# Sensor_Acquisition_Board_Rev4.net
KiCad netlist of a schematic drawn in EAGLE
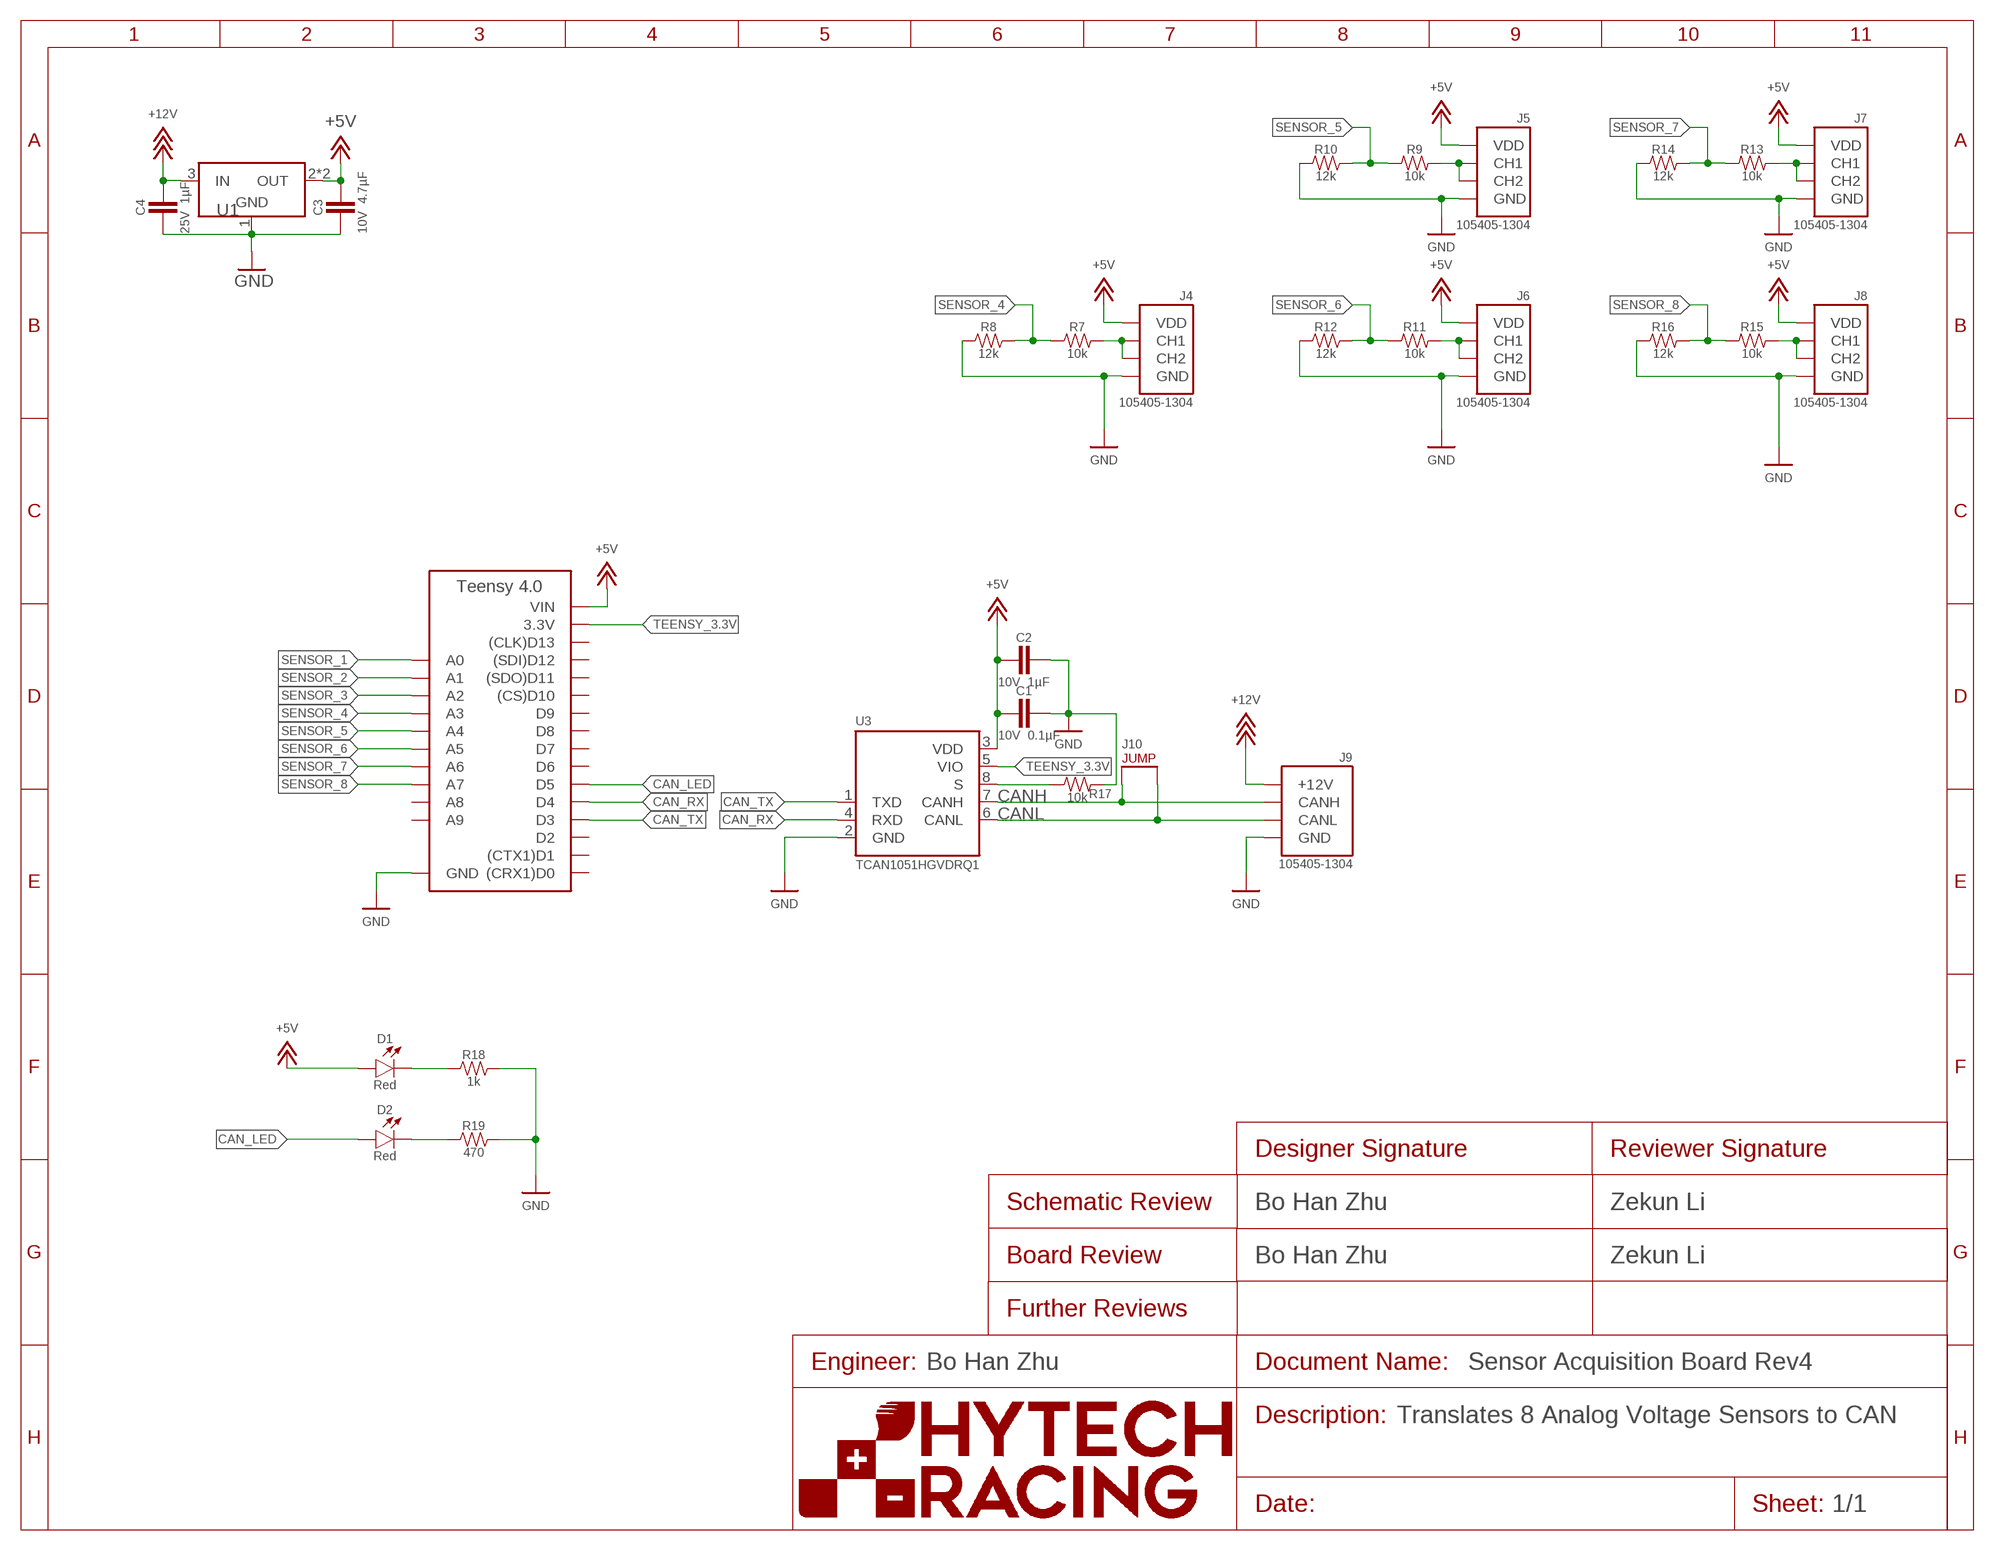
[diagram p0: schematic, sheet 1]

(export (version "E")
  (design (tool "Eeschema 10.0.6"))
  (components
    (comp (ref "A2")
      (value "TEENSY_4.0")
      (footprint "eagle-import:TEENSY_SHORT")
      (libsource (lib "eagle-import") (part "TEENSY_4.0"))
    )
    (comp (ref "C1")
      (value "CAPACITOR_0603_10V_0.1UF")
      (footprint "eagle-import:0603-CAP")
      (fields
        (field (name "CAPACITANCE") "0.1µF")
        (field (name "MANUFACTURER") "Vishay Vitramon")
        (field (name "MPN") "VJ0603Y104JXQPW1BC")
        (field (name "TOLERANCE") "5%")
        (field (name "VOLTAGE") "10V")
      )
      (libsource (lib "eagle-import") (part "CAPACITOR_?_060310V_0.1UF"))
    )
    (comp (ref "C2")
      (value "CAPACITOR_0603_10V_1UF")
      (footprint "eagle-import:0603-CAP")
      (fields
        (field (name "CAPACITANCE") "1µF")
        (field (name "MANUFACTURER") "Yageo")
        (field (name "MPN") "CC0603KRX7R6BB105")
        (field (name "TOLERANCE") "10%")
        (field (name "VOLTAGE") "10V")
      )
      (libsource (lib "eagle-import") (part "CAPACITOR_?_060310V_1UF"))
    )
    (comp (ref "C3")
      (value "CAPACITOR_0603_10V_4.7UF")
      (footprint "eagle-import:0603-CAP")
      (fields
        (field (name "CAPACITANCE") "4.7µF")
        (field (name "MANUFACTURER") "Samsung Electro-Mechanics")
        (field (name "MPN") "CL10A475KP8NNNC")
        (field (name "TOLERANCE") "10%")
        (field (name "VOLTAGE") "10V")
      )
      (libsource (lib "eagle-import") (part "CAPACITOR_?_060310V_4.7UF"))
    )
    (comp (ref "C4")
      (value "CAPACITOR_0603_25V_1UF")
      (footprint "eagle-import:0603-CAP")
      (fields
        (field (name "CAPACITANCE") "1µF")
        (field (name "MANUFACTURER") "Samsung Electro-Mechanics")
        (field (name "MPN") "CL10B105KA8NNNC")
        (field (name "TOLERANCE") "10%")
        (field (name "VOLTAGE") "25V")
      )
      (libsource (lib "eagle-import") (part "CAPACITOR_?_060325V_1UF"))
    )
    (comp (ref "D1")
      (value "LED_0603_RED")
      (footprint "eagle-import:0603-LED")
      (fields
        (field (name "COLOR") "Red")
        (field (name "MANUFACTURER") "Kingbright")
        (field (name "MPN") "APT1608SECK/J3-PRV")
      )
      (libsource (lib "eagle-import") (part "LED_?_0603RED"))
    )
    (comp (ref "D2")
      (value "LED_0603_RED")
      (footprint "eagle-import:0603-LED")
      (fields
        (field (name "COLOR") "Red")
        (field (name "MANUFACTURER") "Kingbright")
        (field (name "MPN") "APT1608SECK/J3-PRV")
      )
      (libsource (lib "eagle-import") (part "LED_?_0603RED"))
    )
    (comp (ref "J4")
      (value "CONNECTOR-SENSOR_NF_S_RA_BLACK")
      (footprint "eagle-import:MOLEX_NANOFIT_SMD_RIGHTANGLE_04")
      (fields (field (name "MANUFACTURER") "Molex") (field (name "MPN") "105405-1304"))
      (libsource (lib "eagle-import") (part "CONNECTOR-SENSOR_?_NF_S_RABLACK"))
    )
    (comp (ref "J5")
      (value "CONNECTOR-SENSOR_NF_S_RA_BLACK")
      (footprint "eagle-import:MOLEX_NANOFIT_SMD_RIGHTANGLE_04")
      (fields (field (name "MANUFACTURER") "Molex") (field (name "MPN") "105405-1304"))
      (libsource (lib "eagle-import") (part "CONNECTOR-SENSOR_?_NF_S_RABLACK"))
    )
    (comp (ref "J6")
      (value "CONNECTOR-SENSOR_NF_S_RA_BLACK")
      (footprint "eagle-import:MOLEX_NANOFIT_SMD_RIGHTANGLE_04")
      (fields (field (name "MANUFACTURER") "Molex") (field (name "MPN") "105405-1304"))
      (libsource (lib "eagle-import") (part "CONNECTOR-SENSOR_?_NF_S_RABLACK"))
    )
    (comp (ref "J7")
      (value "CONNECTOR-SENSOR_NF_S_RA_BLACK")
      (footprint "eagle-import:MOLEX_NANOFIT_SMD_RIGHTANGLE_04")
      (fields (field (name "MANUFACTURER") "Molex") (field (name "MPN") "105405-1304"))
      (libsource (lib "eagle-import") (part "CONNECTOR-SENSOR_?_NF_S_RABLACK"))
    )
    (comp (ref "J8")
      (value "CONNECTOR-SENSOR_NF_S_RA_BLACK")
      (footprint "eagle-import:MOLEX_NANOFIT_SMD_RIGHTANGLE_04")
      (fields (field (name "MANUFACTURER") "Molex") (field (name "MPN") "105405-1304"))
      (libsource (lib "eagle-import") (part "CONNECTOR-SENSOR_?_NF_S_RABLACK"))
    )
    (comp (ref "J9")
      (value "CONNECTOR-CAN_NF_S_RA_BLACK")
      (footprint "eagle-import:MOLEX_NANOFIT_SMD_RIGHTANGLE_04")
      (fields (field (name "MANUFACTURER") "Molex") (field (name "MPN") "105405-1304"))
      (libsource (lib "eagle-import") (part "CONNECTOR-CAN_?_NF_S_RABLACK"))
    )
    (comp (ref "J10")
      (value "JUMPER_0603_")
      (footprint "eagle-import:0603-RES")
      (fields (field (name "MPN") "RC0603FR-130RL") (field (name "MANUFACTURER") "YAGEO"))
      (libsource (lib "eagle-import") (part "JUMPER_?_0603"))
    )
    (comp (ref "R7")
      (value "RESISTOR_0603_10K")
      (footprint "eagle-import:0603-RES")
      (fields
        (field (name "MANUFACTURER") "Yageo")
        (field (name "MPN") "RC0603FR-0710KL")
        (field (name "POWER") "0.1W")
        (field (name "RESISTANCE") "10k")
      )
      (libsource (lib "eagle-import") (part "RESISTOR_?_060310K"))
    )
    (comp (ref "R8")
      (value "RESISTOR_0603_12K")
      (footprint "eagle-import:0603-RES")
      (fields
        (field (name "MANUFACTURER") "Yageo")
        (field (name "MPN") "RC0603FR-0712KL")
        (field (name "POWER") "0.1W")
        (field (name "RESISTANCE") "12k")
      )
      (libsource (lib "eagle-import") (part "RESISTOR_?_060312K"))
    )
    (comp (ref "R9")
      (value "RESISTOR_0603_10K")
      (footprint "eagle-import:0603-RES")
      (fields
        (field (name "MANUFACTURER") "Yageo")
        (field (name "MPN") "RC0603FR-0710KL")
        (field (name "POWER") "0.1W")
        (field (name "RESISTANCE") "10k")
      )
      (libsource (lib "eagle-import") (part "RESISTOR_?_060310K"))
    )
    (comp (ref "R10")
      (value "RESISTOR_0603_12K")
      (footprint "eagle-import:0603-RES")
      (fields
        (field (name "MANUFACTURER") "Yageo")
        (field (name "MPN") "RC0603FR-0712KL")
        (field (name "POWER") "0.1W")
        (field (name "RESISTANCE") "12k")
      )
      (libsource (lib "eagle-import") (part "RESISTOR_?_060312K"))
    )
    (comp (ref "R11")
      (value "RESISTOR_0603_10K")
      (footprint "eagle-import:0603-RES")
      (fields
        (field (name "MANUFACTURER") "Yageo")
        (field (name "MPN") "RC0603FR-0710KL")
        (field (name "POWER") "0.1W")
        (field (name "RESISTANCE") "10k")
      )
      (libsource (lib "eagle-import") (part "RESISTOR_?_060310K"))
    )
    (comp (ref "R12")
      (value "RESISTOR_0603_12K")
      (footprint "eagle-import:0603-RES")
      (fields
        (field (name "MANUFACTURER") "Yageo")
        (field (name "MPN") "RC0603FR-0712KL")
        (field (name "POWER") "0.1W")
        (field (name "RESISTANCE") "12k")
      )
      (libsource (lib "eagle-import") (part "RESISTOR_?_060312K"))
    )
    (comp (ref "R13")
      (value "RESISTOR_0603_10K")
      (footprint "eagle-import:0603-RES")
      (fields
        (field (name "MANUFACTURER") "Yageo")
        (field (name "MPN") "RC0603FR-0710KL")
        (field (name "POWER") "0.1W")
        (field (name "RESISTANCE") "10k")
      )
      (libsource (lib "eagle-import") (part "RESISTOR_?_060310K"))
    )
    (comp (ref "R14")
      (value "RESISTOR_0603_12K")
      (footprint "eagle-import:0603-RES")
      (fields
        (field (name "MANUFACTURER") "Yageo")
        (field (name "MPN") "RC0603FR-0712KL")
        (field (name "POWER") "0.1W")
        (field (name "RESISTANCE") "12k")
      )
      (libsource (lib "eagle-import") (part "RESISTOR_?_060312K"))
    )
    (comp (ref "R15")
      (value "RESISTOR_0603_10K")
      (footprint "eagle-import:0603-RES")
      (fields
        (field (name "MANUFACTURER") "Yageo")
        (field (name "MPN") "RC0603FR-0710KL")
        (field (name "POWER") "0.1W")
        (field (name "RESISTANCE") "10k")
      )
      (libsource (lib "eagle-import") (part "RESISTOR_?_060310K"))
    )
    (comp (ref "R16")
      (value "RESISTOR_0603_12K")
      (footprint "eagle-import:0603-RES")
      (fields
        (field (name "MANUFACTURER") "Yageo")
        (field (name "MPN") "RC0603FR-0712KL")
        (field (name "POWER") "0.1W")
        (field (name "RESISTANCE") "12k")
      )
      (libsource (lib "eagle-import") (part "RESISTOR_?_060312K"))
    )
    (comp (ref "R17")
      (value "RESISTOR_0603_10K")
      (footprint "eagle-import:0603-RES")
      (fields
        (field (name "MANUFACTURER") "Yageo")
        (field (name "MPN") "RC0603FR-0710KL")
        (field (name "POWER") "0.1W")
        (field (name "RESISTANCE") "10k")
      )
      (libsource (lib "eagle-import") (part "RESISTOR_?_060310K"))
    )
    (comp (ref "R18")
      (value "RESISTOR_0603_1K")
      (footprint "eagle-import:0603-RES")
      (fields
        (field (name "MANUFACTURER") "Yageo")
        (field (name "MPN") "RC0603FR-071KL")
        (field (name "POWER") "0.1W")
        (field (name "RESISTANCE") "1k")
      )
      (libsource (lib "eagle-import") (part "RESISTOR_?_06031K"))
    )
    (comp (ref "R19")
      (value "RESISTOR_0603_470")
      (footprint "eagle-import:0603-RES")
      (fields
        (field (name "MANUFACTURER") "Panasonic Electronic Components")
        (field (name "MPN") "ERJ-PA3F4700V")
        (field (name "POWER") "0.25W")
        (field (name "RESISTANCE") "470")
      )
      (libsource (lib "eagle-import") (part "RESISTOR_?_0603470"))
    )
    (comp (ref "U1")
      (value "VOLTAGE_REGULATOR_SOT-223_5V")
      (footprint "eagle-import:SOT-223")
      (fields (field (name "MANUFACTURER") "STMicroelectronics") (field (name "MPN") "LDL1117S50R"))
      (libsource (lib "eagle-import") (part "VOLTAGE_REGULATOR_?_SOT-2235V"))
    )
    (comp (ref "U3")
      (value "TCAN1051HQV-Q1")
      (footprint "eagle-import:SOIC-08(NARROW,0.15_)")
      (fields (field (name "MANUFACTURER") "Texas Instruments") (field (name "MPN") "TCAN1051HGVDRQ1"))
      (libsource (lib "eagle-import") (part "TCAN1051V-Q1HQ"))
    )
  )
  (nets
    (net (code "1") (name "+5V") (class "Default")
      (node (ref "A2") (pin "VIN") (pinfunction "VIN_VIN") (pintype "power_in"))
      (node (ref "C1") (pin "2") (pinfunction "2_2") (pintype "passive"))
      (node (ref "C2") (pin "2") (pinfunction "2_2") (pintype "passive"))
      (node (ref "C3") (pin "1") (pinfunction "1_1") (pintype "passive"))
      (node (ref "D1") (pin "2") (pinfunction "A_2") (pintype "passive"))
      (node (ref "J4") (pin "1") (pinfunction "VDD_1") (pintype "power_in"))
      (node (ref "J5") (pin "1") (pinfunction "VDD_1") (pintype "power_in"))
      (node (ref "J6") (pin "1") (pinfunction "VDD_1") (pintype "power_in"))
      (node (ref "J7") (pin "1") (pinfunction "VDD_1") (pintype "power_in"))
      (node (ref "J8") (pin "1") (pinfunction "VDD_1") (pintype "power_in"))
      (node (ref "U1") (pin "2") (pinfunction "OUT_2") (pintype "power_in"))
      (node (ref "U1") (pin "4") (pinfunction "OUT_4") (pintype "power_in"))
      (node (ref "U3") (pin "3") (pinfunction "VDD_3") (pintype "power_in"))
    )
    (net (code "2") (name "+12V") (class "Default")
      (node (ref "C4") (pin "1") (pinfunction "1_1") (pintype "passive"))
      (node (ref "J9") (pin "1") (pinfunction "+12V_1") (pintype "power_in"))
      (node (ref "U1") (pin "3") (pinfunction "IN_3") (pintype "power_in"))
    )
    (net (code "3") (name "/CANH") (class "Default")
      (node (ref "J10") (pin "1") (pinfunction "1_1") (pintype "passive"))
      (node (ref "J9") (pin "4") (pinfunction "CANH_4") (pintype "bidirectional"))
      (node (ref "U3") (pin "7") (pinfunction "CANH_7") (pintype "output"))
    )
    (net (code "4") (name "/CANL") (class "Default")
      (node (ref "J10") (pin "2") (pinfunction "2_2") (pintype "passive"))
      (node (ref "J9") (pin "3") (pinfunction "CANL_3") (pintype "bidirectional"))
      (node (ref "U3") (pin "6") (pinfunction "CANL_6") (pintype "bidirectional"))
    )
    (net (code "5") (name "CAN_LED") (class "Default")
      (node (ref "A2") (pin "D5") (pinfunction "D5_D5") (pintype "bidirectional"))
      (node (ref "D2") (pin "2") (pinfunction "A_2") (pintype "passive"))
    )
    (net (code "6") (name "CAN_RX") (class "Default")
      (node (ref "A2") (pin "D4") (pinfunction "D4_D4") (pintype "bidirectional"))
      (node (ref "U3") (pin "4") (pinfunction "RXD_4") (pintype "output"))
    )
    (net (code "7") (name "CAN_TX") (class "Default")
      (node (ref "A2") (pin "D3") (pinfunction "D3_D3") (pintype "bidirectional"))
      (node (ref "U3") (pin "1") (pinfunction "TXD_1") (pintype "input"))
    )
    (net (code "8") (name "GND") (class "Default")
      (node (ref "A2") (pin "AGND/GND") (pinfunction "GND_AGND/GND") (pintype "power_in"))
      (node (ref "A2") (pin "GND") (pinfunction "GND_GND") (pintype "power_in"))
      (node (ref "C1") (pin "1") (pinfunction "1_1") (pintype "passive"))
      (node (ref "C2") (pin "1") (pinfunction "1_1") (pintype "passive"))
      (node (ref "C3") (pin "2") (pinfunction "2_2") (pintype "passive"))
      (node (ref "C4") (pin "2") (pinfunction "2_2") (pintype "passive"))
      (node (ref "J4") (pin "2") (pinfunction "GND_2") (pintype "power_in"))
      (node (ref "J5") (pin "2") (pinfunction "GND_2") (pintype "power_in"))
      (node (ref "J6") (pin "2") (pinfunction "GND_2") (pintype "power_in"))
      (node (ref "J7") (pin "2") (pinfunction "GND_2") (pintype "power_in"))
      (node (ref "J8") (pin "2") (pinfunction "GND_2") (pintype "power_in"))
      (node (ref "J9") (pin "2") (pinfunction "GND_2") (pintype "power_in"))
      (node (ref "R10") (pin "1") (pinfunction "1_1") (pintype "passive"))
      (node (ref "R12") (pin "1") (pinfunction "1_1") (pintype "passive"))
      (node (ref "R14") (pin "1") (pinfunction "1_1") (pintype "passive"))
      (node (ref "R16") (pin "1") (pinfunction "1_1") (pintype "passive"))
      (node (ref "R17") (pin "2") (pinfunction "2_2") (pintype "passive"))
      (node (ref "R18") (pin "2") (pinfunction "2_2") (pintype "passive"))
      (node (ref "R19") (pin "2") (pinfunction "2_2") (pintype "passive"))
      (node (ref "R8") (pin "1") (pinfunction "1_1") (pintype "passive"))
      (node (ref "U1") (pin "1") (pinfunction "GND_1") (pintype "power_in"))
      (node (ref "U3") (pin "2") (pinfunction "GND_2") (pintype "power_in"))
    )
    (net (code "9") (name "Net-(D1-C)") (class "Default")
      (node (ref "D1") (pin "1") (pinfunction "C_1") (pintype "passive"))
      (node (ref "R18") (pin "1") (pinfunction "1_1") (pintype "passive"))
    )
    (net (code "10") (name "Net-(D2-C)") (class "Default")
      (node (ref "D2") (pin "1") (pinfunction "C_1") (pintype "passive"))
      (node (ref "R19") (pin "1") (pinfunction "1_1") (pintype "passive"))
    )
    (net (code "11") (name "Net-(J4-CH1)") (class "Default")
      (node (ref "J4") (pin "3") (pinfunction "CH1_3") (pintype "output"))
      (node (ref "J4") (pin "4") (pinfunction "CH2_4") (pintype "output"))
      (node (ref "R7") (pin "2") (pinfunction "2_2") (pintype "passive"))
    )
    (net (code "12") (name "Net-(J5-CH1)") (class "Default")
      (node (ref "J5") (pin "3") (pinfunction "CH1_3") (pintype "output"))
      (node (ref "J5") (pin "4") (pinfunction "CH2_4") (pintype "output"))
      (node (ref "R9") (pin "2") (pinfunction "2_2") (pintype "passive"))
    )
    (net (code "13") (name "Net-(J6-CH1)") (class "Default")
      (node (ref "J6") (pin "3") (pinfunction "CH1_3") (pintype "output"))
      (node (ref "J6") (pin "4") (pinfunction "CH2_4") (pintype "output"))
      (node (ref "R11") (pin "2") (pinfunction "2_2") (pintype "passive"))
    )
    (net (code "14") (name "Net-(J7-CH1)") (class "Default")
      (node (ref "J7") (pin "3") (pinfunction "CH1_3") (pintype "output"))
      (node (ref "J7") (pin "4") (pinfunction "CH2_4") (pintype "output"))
      (node (ref "R13") (pin "2") (pinfunction "2_2") (pintype "passive"))
    )
    (net (code "15") (name "Net-(J8-CH1)") (class "Default")
      (node (ref "J8") (pin "3") (pinfunction "CH1_3") (pintype "output"))
      (node (ref "J8") (pin "4") (pinfunction "CH2_4") (pintype "output"))
      (node (ref "R15") (pin "2") (pinfunction "2_2") (pintype "passive"))
    )
    (net (code "16") (name "Net-(U3-S)") (class "Default")
      (node (ref "R17") (pin "1") (pinfunction "1_1") (pintype "passive"))
      (node (ref "U3") (pin "8") (pinfunction "S_8") (pintype "input"))
    )
    (net (code "17") (name "SENSOR_1") (class "Default")
      (node (ref "A2") (pin "D14") (pinfunction "A0_D14") (pintype "bidirectional"))
    )
    (net (code "18") (name "SENSOR_2") (class "Default")
      (node (ref "A2") (pin "D15") (pinfunction "A1_D15") (pintype "bidirectional"))
    )
    (net (code "19") (name "SENSOR_3") (class "Default")
      (node (ref "A2") (pin "D16") (pinfunction "A2_D16") (pintype "bidirectional"))
    )
    (net (code "20") (name "SENSOR_4") (class "Default")
      (node (ref "A2") (pin "D17") (pinfunction "A3_D17") (pintype "bidirectional"))
      (node (ref "R7") (pin "1") (pinfunction "1_1") (pintype "passive"))
      (node (ref "R8") (pin "2") (pinfunction "2_2") (pintype "passive"))
    )
    (net (code "21") (name "SENSOR_5") (class "Default")
      (node (ref "A2") (pin "D18") (pinfunction "A4_D18") (pintype "bidirectional"))
      (node (ref "R10") (pin "2") (pinfunction "2_2") (pintype "passive"))
      (node (ref "R9") (pin "1") (pinfunction "1_1") (pintype "passive"))
    )
    (net (code "22") (name "SENSOR_6") (class "Default")
      (node (ref "A2") (pin "D19") (pinfunction "A5_D19") (pintype "bidirectional"))
      (node (ref "R11") (pin "1") (pinfunction "1_1") (pintype "passive"))
      (node (ref "R12") (pin "2") (pinfunction "2_2") (pintype "passive"))
    )
    (net (code "23") (name "SENSOR_7") (class "Default")
      (node (ref "A2") (pin "D20") (pinfunction "A6_D20") (pintype "bidirectional"))
      (node (ref "R13") (pin "1") (pinfunction "1_1") (pintype "passive"))
      (node (ref "R14") (pin "2") (pinfunction "2_2") (pintype "passive"))
    )
    (net (code "24") (name "SENSOR_8") (class "Default")
      (node (ref "A2") (pin "D21") (pinfunction "A7_D21") (pintype "bidirectional"))
      (node (ref "R15") (pin "1") (pinfunction "1_1") (pintype "passive"))
      (node (ref "R16") (pin "2") (pinfunction "2_2") (pintype "passive"))
    )
    (net (code "25") (name "TEENSY_3.3V") (class "Default")
      (node (ref "A2") (pin "3.3V") (pinfunction "3.3V_3.3V") (pintype "power_in"))
      (node (ref "U3") (pin "5") (pinfunction "VIO_5") (pintype "power_in"))
    )
    (net (code "26") (name "unconnected-(A2-(CLK)D13-PadD13)") (class "Default")
      (node (ref "A2") (pin "D13") (pinfunction "(CLK)D13_D13") (pintype "bidirectional"))
    )
    (net (code "27") (name "unconnected-(A2-(CRX1)D0-PadD0)") (class "Default")
      (node (ref "A2") (pin "D0") (pinfunction "(CRX1)D0_D0") (pintype "bidirectional"))
    )
    (net (code "28") (name "unconnected-(A2-(CS)D10-PadD10)") (class "Default")
      (node (ref "A2") (pin "D10") (pinfunction "(CS)D10_D10") (pintype "bidirectional"))
    )
    (net (code "29") (name "unconnected-(A2-(CTX1)D1-PadD1)") (class "Default")
      (node (ref "A2") (pin "D1") (pinfunction "(CTX1)D1_D1") (pintype "bidirectional"))
    )
    (net (code "30") (name "unconnected-(A2-(SDI)D12-PadD12)") (class "Default")
      (node (ref "A2") (pin "D12") (pinfunction "(SDI)D12_D12") (pintype "bidirectional"))
    )
    (net (code "31") (name "unconnected-(A2-(SDO)D11-PadD11)") (class "Default")
      (node (ref "A2") (pin "D11") (pinfunction "(SDO)D11_D11") (pintype "bidirectional"))
    )
    (net (code "32") (name "unconnected-(A2-A8-PadD22)") (class "Default")
      (node (ref "A2") (pin "D22") (pinfunction "A8_D22") (pintype "bidirectional"))
    )
    (net (code "33") (name "unconnected-(A2-A9-PadD23)") (class "Default")
      (node (ref "A2") (pin "D23") (pinfunction "A9_D23") (pintype "bidirectional"))
    )
    (net (code "34") (name "unconnected-(A2-PadD2)") (class "Default")
      (node (ref "A2") (pin "D2") (pinfunction "D2_D2") (pintype "bidirectional"))
    )
    (net (code "35") (name "unconnected-(A2-PadD6)") (class "Default")
      (node (ref "A2") (pin "D6") (pinfunction "D6_D6") (pintype "bidirectional"))
    )
    (net (code "36") (name "unconnected-(A2-PadD7)") (class "Default")
      (node (ref "A2") (pin "D7") (pinfunction "D7_D7") (pintype "bidirectional"))
    )
    (net (code "37") (name "unconnected-(A2-PadD8)") (class "Default")
      (node (ref "A2") (pin "D8") (pinfunction "D8_D8") (pintype "bidirectional"))
    )
    (net (code "38") (name "unconnected-(A2-PadD9)") (class "Default")
      (node (ref "A2") (pin "D9") (pinfunction "D9_D9") (pintype "bidirectional"))
    )
  )
)
